# transmitter.net
KiCad netlist of a schematic drawn in Altium Designer
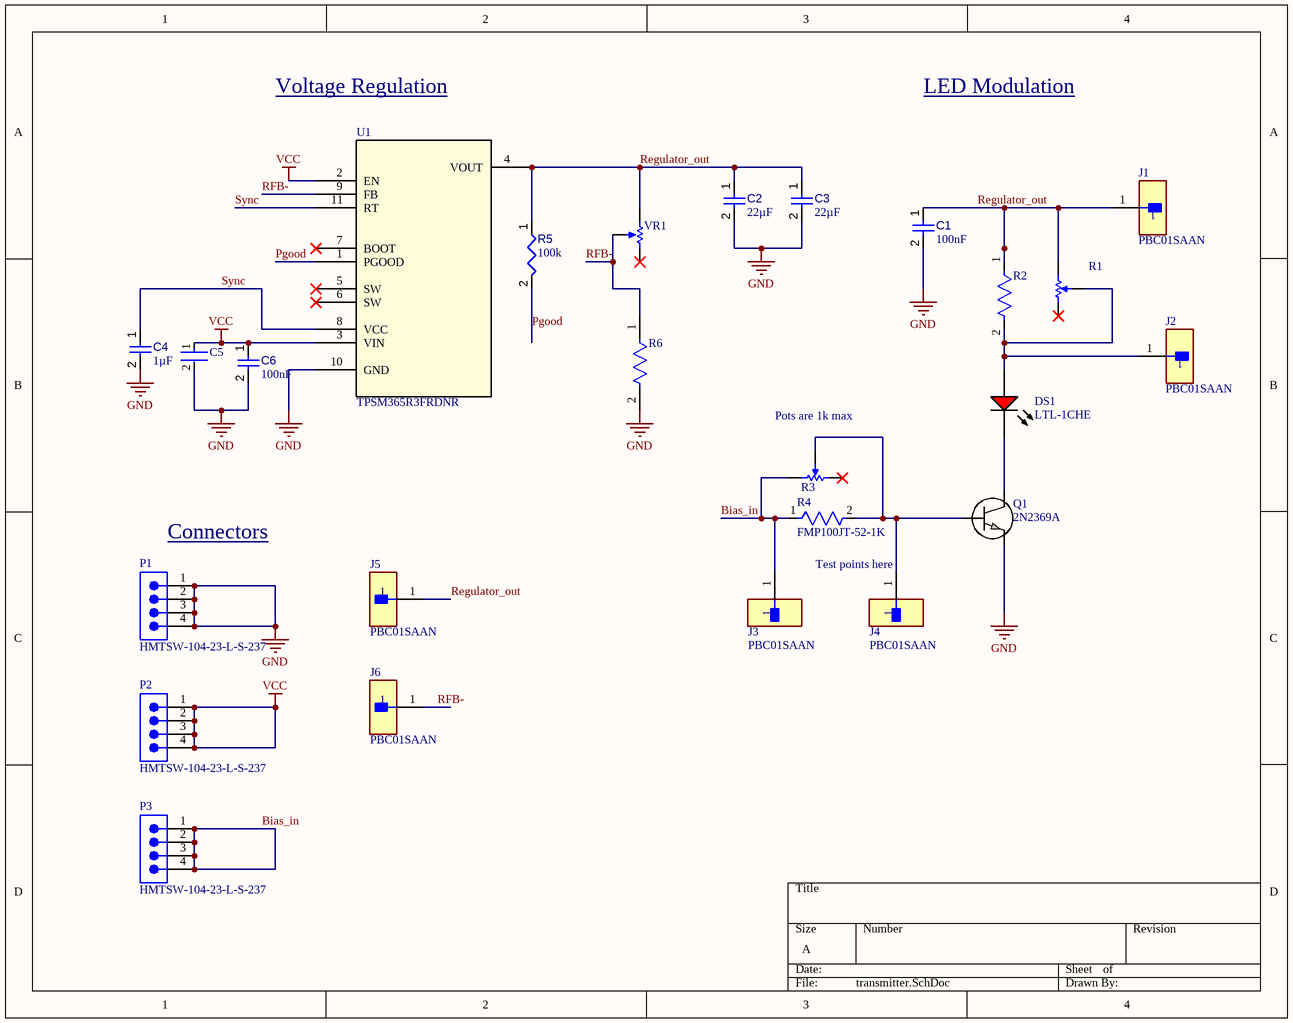
[diagram p0: transmitter.SchDoc]

(export (version "E")
  (design (tool "Eeschema 10.0.6"))
  (components
    (comp (ref "C1")
      (value "100nF")
      (footprint "CAPC0402(1005)60_L")
      (description "Chip Capacitor, 100nF +/-20%, 50V, 0402, Thickness 0.6 mm")
      (fields (field (name "TOLERANCE") "10%") (field (name "Comment") "Capacitor 100nF +/-20% 50V 0402"))
      (libsource (lib "XCOM_capstone") (part "CAP-NP-2"))
    )
    (comp (ref "C2")
      (value "22µF")
      (footprint "CAPC0805(2012)145_L")
      (description "Chip Capacitor, 22µF +/-40%, 16V, 0805, Thickness 1.45 mm")
      (fields (field (name "TOLERANCE") "5%") (field (name "Comment") "Capacitor 22µF +/-40% 16V 0805"))
      (libsource (lib "XCOM_capstone") (part "CAP-NP-2"))
    )
    (comp (ref "C3")
      (value "22µF")
      (footprint "CAPC0805(2012)145_L")
      (description "Chip Capacitor, 22µF +/-40%, 16V, 0805, Thickness 1.45 mm")
      (fields (field (name "TOLERANCE") "5%") (field (name "Comment") "Capacitor 22µF +/-40% 16V 0805"))
      (libsource (lib "XCOM_capstone") (part "CAP-NP-2"))
    )
    (comp (ref "C4")
      (value "1µF")
      (footprint "CAPC0603(1608)100_L")
      (description "Chip Capacitor, 1µF +/-0.1%, 25V, 0603, Thickness 1 mm")
      (fields (field (name "TOLERANCE") "20%") (field (name "Comment") "Capacitor 1µF +/-0.1% 25V 0603"))
      (libsource (lib "XCOM_capstone") (part "CAP-NP-2"))
    )
    (comp (ref "C5")
      (value "GRM21BD72A225ME01K")
      (footprint "FP-GRM21B-0_2-e0_2_0_7-IPC_B")
      (description "CAP CER 2.2UF 100V X7T 0805")
      (libsource (lib "Altium Content Vault") (part "b4654b650e69147ec39a6b967a45e02"))
    )
    (comp (ref "C6")
      (value "100nF")
      (footprint "CAPC2013X95X50LL10T25")
      (description "Chip Capacitor, 100 nF, +/- 10%, 50 V, 0805 (2012 Metric)")
      (fields (field (name "TOLERANCE") "10%") (field (name "Comment") "Capacitor 100 nF +/-10% 50 V 0805"))
      (libsource (lib "XCOM_capstone") (part "CAP-NP-2"))
    )
    (comp (ref "DS1")
      (value "LTL-1CHE")
      (footprint "INDPR60-254-520X380X650")
      (description "LED Uni-Color Red, 100 mW, 30 mA, -55 to 100 degC, 2-Pin THD, RoHS, Bulk")
      (fields (field (name "MANUFACTURER") "Lite-On"))
      (libsource (lib "XCOM_capstone") (part "LED-RED-AK-2"))
    )
    (comp (ref "J1")
      (value "PBC01SAAN")
      (footprint "FP-PBC01SAAN-MFG")
      (description "CONN HEADER VERT 1POS")
      (libsource (lib "Altium Content Vault") (part "dd45045ce8184df9e99e12baf3f412c"))
    )
    (comp (ref "J2")
      (value "PBC01SAAN")
      (footprint "FP-PBC01SAAN-MFG")
      (description "CONN HEADER VERT 1POS")
      (libsource (lib "Altium Content Vault") (part "dd45045ce8184df9e99e12baf3f412c"))
    )
    (comp (ref "J3")
      (value "PBC01SAAN")
      (footprint "FP-PBC01SAAN-MFG")
      (description "CONN HEADER VERT 1POS")
      (libsource (lib "") (part "dd45045ce8184df9e99e12baf3f412c_1"))
    )
    (comp (ref "J4")
      (value "PBC01SAAN")
      (footprint "FP-PBC01SAAN-MFG")
      (description "CONN HEADER VERT 1POS")
      (libsource (lib "") (part "dd45045ce8184df9e99e12baf3f412c_1"))
    )
    (comp (ref "J5")
      (value "PBC01SAAN")
      (footprint "FP-PBC01SAAN-MFG")
      (description "CONN HEADER VERT 1POS")
      (libsource (lib "") (part "dd45045ce8184df9e99e12baf3f412c_2"))
    )
    (comp (ref "J6")
      (value "PBC01SAAN")
      (footprint "FP-PBC01SAAN-MFG")
      (description "CONN HEADER VERT 1POS")
      (libsource (lib "") (part "dd45045ce8184df9e99e12baf3f412c_2"))
    )
    (comp (ref "P1")
      (value "HMTSW-104-23-L-S-237")
      (footprint "SMTC-HMTSW-104-23-X-S-237")
      (fields (field (name "MANUFACTURER") "Samtec"))
      (libsource (lib "Altium Content Vault") (part "SMTC-HMTSW-104-23-X-S-237"))
    )
    (comp (ref "P2")
      (value "HMTSW-104-23-L-S-237")
      (footprint "SMTC-HMTSW-104-23-X-S-237")
      (fields (field (name "MANUFACTURER") "Samtec"))
      (libsource (lib "Altium Content Vault") (part "SMTC-HMTSW-104-23-X-S-237"))
    )
    (comp (ref "P3")
      (value "HMTSW-104-23-L-S-237")
      (footprint "SMTC-HMTSW-104-23-X-S-237")
      (fields (field (name "MANUFACTURER") "Samtec"))
      (libsource (lib "Altium Content Vault") (part "SMTC-HMTSW-104-23-X-S-237"))
    )
    (comp (ref "Q1")
      (value "2N2369A")
      (footprint "TO-18_STM")
      (description "Description")
      (fields (field (name "COPYRIGHT") "Copyright (C) 2025 Ultra Librarian. All rights reserved."))
      (libsource (lib "XCOM_capstone") (part "2N2369A"))
    )
    (comp (ref "R1")
      (value "3296W-1-102LF")
      (footprint "BOUR-3296W-1-3")
      (description "Square Trimpot(R) Trimming Potentiometer, 1000 Ohm, -55 to 125 degC, 3-Pin THD, RoHS, Tube")
      (fields (field (name "MANUFACTURER") "Bourns") (field (name "POWER") "500mW"))
      (libsource (lib "XCOM_capstone") (part "RES-ADJ-3"))
    )
    (comp (ref "R2")
      (value "MBA02040C2200FC100")
      (footprint "FP-MBA0204-MFG")
      (description "RES 220 OHM 0.4W 1% AXIAL")
      (fields
        (field (name "OCTOPART") "https://octopart.com/mba02040c2200fc100-vishay-43743094")
        (field (name "MANUFACTURER") "Vishay BC Components")
      )
      (libsource (lib "Altium Content Vault") (part "1029c3af85768c4190bb7ad29bc67b5"))
    )
    (comp (ref "R3")
      (value "3296W-1-102LF")
      (footprint "BOUR-3296W-1-3")
      (description "Square Trimpot(R) Trimming Potentiometer, 1000 Ohm, -55 to 125 degC, 3-Pin THD, RoHS, Tube")
      (fields (field (name "MANUFACTURER") "Bourns") (field (name "POWER") "500mW"))
      (libsource (lib "XCOM_capstone") (part "RES-ADJ-3"))
    )
    (comp (ref "R4")
      (value "FMP100JT-52-1K")
      (footprint "FP-FMP100-MFG")
      (description "Resistor, 1 kOhm, ± 5%, 1 W, Axial Leaded, Metal Film, High Power Flame Proof")
      (fields (field (name "TOLERANCE") "5%"))
      (libsource (lib "Altium Content Vault") (part "FMP100JT-52-1K"))
    )
    (comp (ref "R5")
      (value "100k")
      (footprint "RESC1608X55X25ML10T15")
      (description "Chip Resistor, 100 KOhm, +/- 1%, 0.1 W, -55 to 155 degC, 0603 (1608 Metric)")
      (fields (field (name "TOLERANCE") "1%") (field (name "POWER") "100mW"))
      (libsource (lib "XCOM_capstone") (part "RES-2"))
    )
    (comp (ref "R6")
      (value "AC2512FK-0710KL")
      (footprint "FP-AC2512-MFG")
      (description "AC2512 10KΩ 1W 1.00%")
      (fields (field (name "MANUFACTURER") "Yageo"))
      (libsource (lib "Altium Content Vault") (part "1029c3af85768c4190bb7ad29bc67b5"))
    )
    (comp (ref "U1")
      (value "TPSM365R3FRDNR")
      (footprint "QFN-FCMOD_365R6FRDN_TEX")
      (fields (field (name "COPYRIGHT") "Copyright (C) 2025 Ultra Librarian. All rights reserved."))
      (libsource (lib "XCOM_capstone") (part "TPSM365R3FRDNR"))
    )
    (comp (ref "VR1")
      (value "3362P-1-104LF")
      (footprint "BOUR-3362P")
      (description "Square Trimpot(R) Trimming Potentiometer, 100 KOhm, 300 V, -55 to 125 degC, 3-Pin THD, RoHS, Tube")
      (fields (field (name "TOLERANCE") "1%"))
      (libsource (lib "Altium Content Vault") (part "RES-POT-3"))
    )
  )
  (nets
    (net (code "2") (name "/Bias_in") (class "Default")
      (node (ref "J3") (pin "1") (pinfunction "1_1") (pintype "passive"))
      (node (ref "P3") (pin "1") (pinfunction "1_1") (pintype "passive"))
      (node (ref "P3") (pin "2") (pinfunction "2_2") (pintype "passive"))
      (node (ref "P3") (pin "3") (pinfunction "3_3") (pintype "passive"))
      (node (ref "P3") (pin "4") (pinfunction "4_4") (pintype "passive"))
      (node (ref "R3") (pin "2") (pinfunction "B_2") (pintype "passive"))
      (node (ref "R4") (pin "1") (pinfunction "1_1") (pintype "passive"))
    )
    (net (code "3") (name "/Pgood") (class "Default")
      (node (ref "R5") (pin "2") (pinfunction "2_2") (pintype "passive"))
      (node (ref "U1") (pin "1") (pinfunction "PGOOD_1") (pintype "passive"))
    )
    (net (code "4") (name "/RFB-") (class "Default")
      (node (ref "J6") (pin "1") (pinfunction "1_1") (pintype "passive"))
      (node (ref "R6") (pin "1") (pinfunction "1_1") (pintype "passive"))
      (node (ref "U1") (pin "9") (pinfunction "FB_9") (pintype "passive"))
      (node (ref "VR1") (pin "2") (pinfunction "S_2") (pintype "passive"))
    )
    (net (code "5") (name "/Regulator_out") (class "Default")
      (node (ref "C1") (pin "1") (pinfunction "1_1") (pintype "passive"))
      (node (ref "C2") (pin "1") (pinfunction "1_1") (pintype "passive"))
      (node (ref "C3") (pin "1") (pinfunction "1_1") (pintype "passive"))
      (node (ref "J1") (pin "1") (pinfunction "1_1") (pintype "passive"))
      (node (ref "J5") (pin "1") (pinfunction "1_1") (pintype "passive"))
      (node (ref "R1") (pin "2") (pinfunction "B_2") (pintype "passive"))
      (node (ref "R2") (pin "1") (pinfunction "1_1") (pintype "passive"))
      (node (ref "R5") (pin "1") (pinfunction "1_1") (pintype "passive"))
      (node (ref "U1") (pin "4") (pinfunction "VOUT_4") (pintype "power_in"))
      (node (ref "VR1") (pin "1") (pinfunction "CCW_1") (pintype "passive"))
    )
    (net (code "6") (name "/Sync") (class "Default")
      (node (ref "C4") (pin "1") (pinfunction "1_1") (pintype "passive"))
      (node (ref "U1") (pin "11") (pinfunction "RT_11") (pintype "passive"))
      (node (ref "U1") (pin "8") (pinfunction "VCC_8") (pintype "power_in"))
    )
    (net (code "7") (name "GND") (class "Default")
      (node (ref "C1") (pin "2") (pinfunction "2_2") (pintype "passive"))
      (node (ref "C2") (pin "2") (pinfunction "2_2") (pintype "passive"))
      (node (ref "C3") (pin "2") (pinfunction "2_2") (pintype "passive"))
      (node (ref "C4") (pin "2") (pinfunction "2_2") (pintype "passive"))
      (node (ref "C5") (pin "2") (pinfunction "2_2") (pintype "passive"))
      (node (ref "C6") (pin "2") (pinfunction "2_2") (pintype "passive"))
      (node (ref "P1") (pin "1") (pinfunction "1_1") (pintype "passive"))
      (node (ref "P1") (pin "2") (pinfunction "2_2") (pintype "passive"))
      (node (ref "P1") (pin "3") (pinfunction "3_3") (pintype "passive"))
      (node (ref "P1") (pin "4") (pinfunction "4_4") (pintype "passive"))
      (node (ref "Q1") (pin "3") (pinfunction "E_3") (pintype "passive"))
      (node (ref "R6") (pin "2") (pinfunction "2_2") (pintype "passive"))
      (node (ref "U1") (pin "10") (pinfunction "GND_10") (pintype "power_in"))
    )
    (net (code "8") (name "Net-(DS1-A)") (class "Default")
      (node (ref "DS1") (pin "1") (pinfunction "A_1") (pintype "passive"))
      (node (ref "J2") (pin "1") (pinfunction "1_1") (pintype "passive"))
      (node (ref "R1") (pin "3") (pinfunction "TAP_3") (pintype "passive"))
      (node (ref "R2") (pin "2") (pinfunction "2_2") (pintype "passive"))
    )
    (net (code "9") (name "Net-(DS1-K)") (class "Default")
      (node (ref "DS1") (pin "2") (pinfunction "K_2") (pintype "passive"))
      (node (ref "Q1") (pin "1") (pinfunction "C_1") (pintype "passive"))
    )
    (net (code "10") (name "Net-(Q1-B)") (class "Default")
      (node (ref "J4") (pin "1") (pinfunction "1_1") (pintype "passive"))
      (node (ref "Q1") (pin "2") (pinfunction "B_2") (pintype "passive"))
      (node (ref "R3") (pin "3") (pinfunction "TAP_3") (pintype "passive"))
      (node (ref "R4") (pin "2") (pinfunction "2_2") (pintype "passive"))
    )
    (net (code "11") (name "VCC") (class "Default")
      (node (ref "C5") (pin "1") (pinfunction "1_1") (pintype "passive"))
      (node (ref "C6") (pin "1") (pinfunction "1_1") (pintype "passive"))
      (node (ref "P2") (pin "1") (pinfunction "1_1") (pintype "passive"))
      (node (ref "P2") (pin "2") (pinfunction "2_2") (pintype "passive"))
      (node (ref "P2") (pin "3") (pinfunction "3_3") (pintype "passive"))
      (node (ref "P2") (pin "4") (pinfunction "4_4") (pintype "passive"))
      (node (ref "U1") (pin "2") (pinfunction "EN_2") (pintype "passive"))
      (node (ref "U1") (pin "3") (pinfunction "VIN_3") (pintype "power_in"))
    )
    (net (code "12") (name "unconnected-(R1-A-Pad1)") (class "Default")
      (node (ref "R1") (pin "1") (pinfunction "A_1") (pintype "passive+no_connect"))
    )
    (net (code "13") (name "unconnected-(R3-A-Pad1)") (class "Default")
      (node (ref "R3") (pin "1") (pinfunction "A_1") (pintype "passive+no_connect"))
    )
    (net (code "14") (name "unconnected-(U1-BOOT-Pad7)") (class "Default")
      (node (ref "U1") (pin "7") (pinfunction "BOOT_7") (pintype "power_in+no_connect"))
    )
    (net (code "15") (name "unconnected-(U1-SW-Pad5)") (class "Default")
      (node (ref "U1") (pin "5") (pinfunction "SW_5") (pintype "power_in+no_connect"))
    )
    (net (code "16") (name "unconnected-(U1-SW-Pad6)") (class "Default")
      (node (ref "U1") (pin "6") (pinfunction "SW_6") (pintype "power_in+no_connect"))
    )
    (net (code "17") (name "unconnected-(VR1-CW-Pad3)") (class "Default")
      (node (ref "VR1") (pin "3") (pinfunction "CW_3") (pintype "passive+no_connect"))
    )
  )
)
